# mcu.net
KiCad netlist of a schematic drawn in Altium Designer
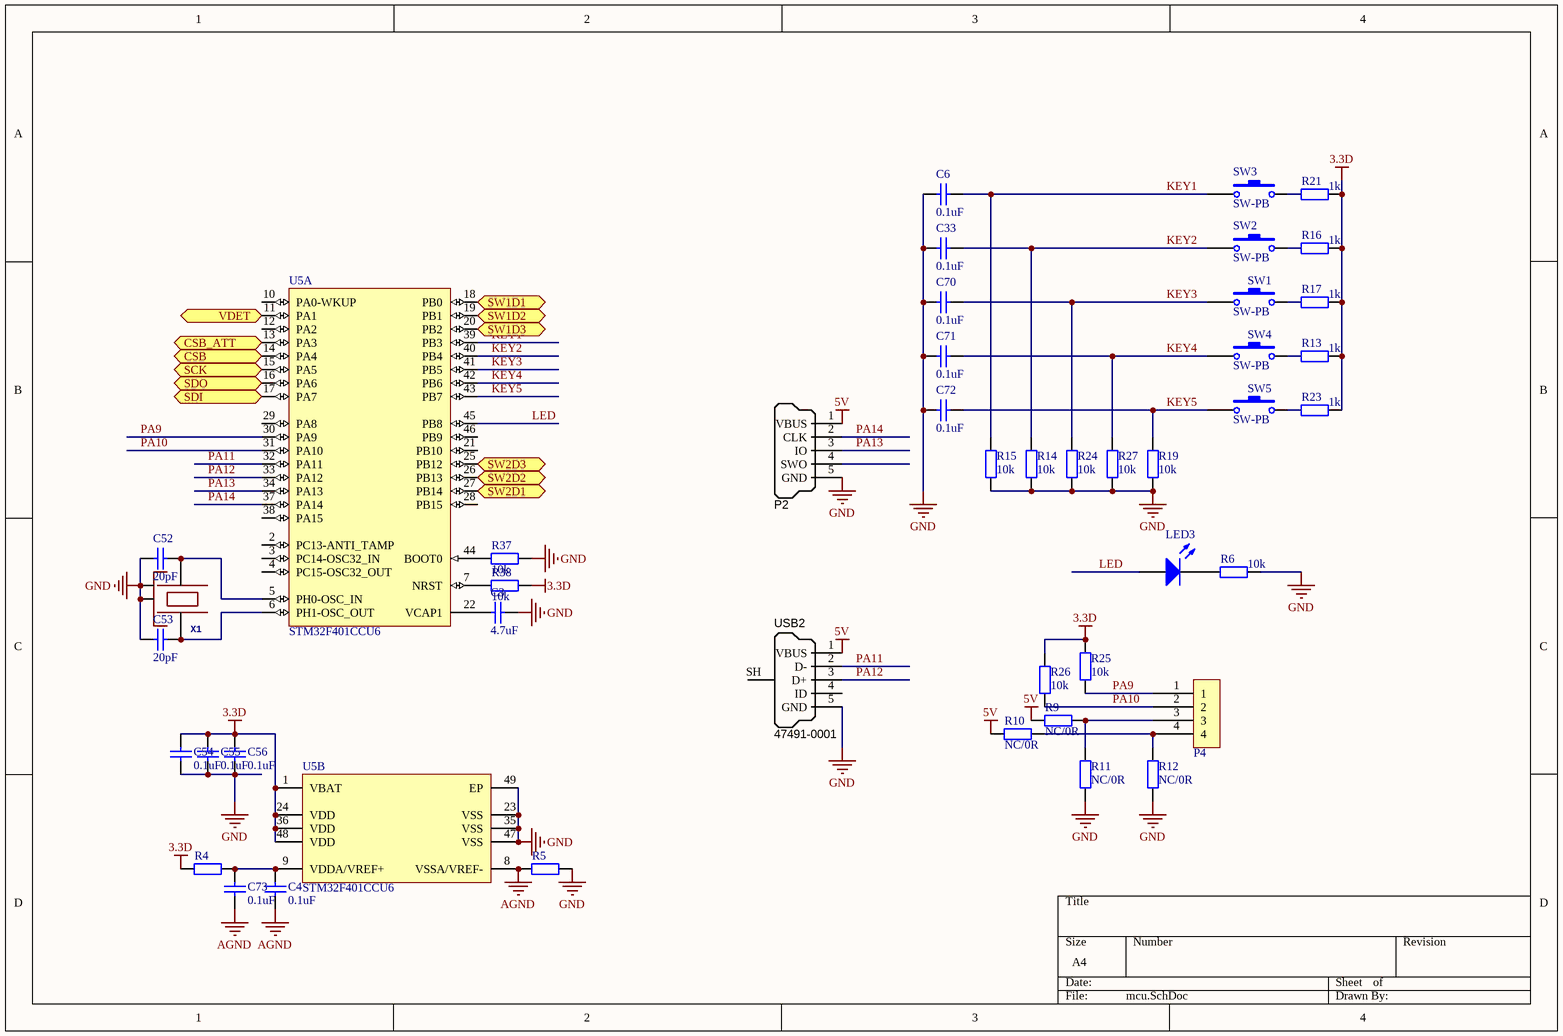
[diagram p0: mcu.SchDoc]

(export (version "E")
  (design (tool "Eeschema 10.0.6"))
  (components
    (comp (ref "C3")
      (value "4.7uF")
      (footprint "0603")
      (description "Capacitor")
      (fields (field (name "Comment") "Cap") (field (name "PUBLISHER") "Altium Limited"))
      (libsource (lib "RTC6705") (part "Cap"))
    )
    (comp (ref "C4")
      (value "0.1uF")
      (footprint "0402")
      (description "Capacitor")
      (fields (field (name "Comment") "Cap") (field (name "PUBLISHER") "Altium Limited"))
      (libsource (lib "RTC6705") (part "Cap"))
    )
    (comp (ref "C6")
      (value "0.1uF")
      (footprint "0402")
      (description "Capacitor")
      (fields (field (name "Comment") "Cap") (field (name "PUBLISHER") "Altium Limited"))
      (libsource (lib "RTC6705") (part "Cap"))
    )
    (comp (ref "C33")
      (value "0.1uF")
      (footprint "0402")
      (description "Capacitor")
      (fields (field (name "Comment") "Cap") (field (name "PUBLISHER") "Altium Limited"))
      (libsource (lib "RTC6705") (part "Cap"))
    )
    (comp (ref "C52")
      (value "20pF")
      (footprint "0402")
      (description "Capacitor")
      (fields (field (name "Comment") "Cap") (field (name "PUBLISHER") "Altium Limited"))
      (libsource (lib "RTC6705") (part "Cap"))
    )
    (comp (ref "C53")
      (value "20pF")
      (footprint "0402")
      (description "Capacitor")
      (fields (field (name "Comment") "Cap") (field (name "PUBLISHER") "Altium Limited"))
      (libsource (lib "RTC6705") (part "Cap"))
    )
    (comp (ref "C54")
      (value "0.1uF")
      (footprint "0402")
      (description "Capacitor")
      (fields (field (name "Comment") "Cap") (field (name "PUBLISHER") "Altium Limited"))
      (libsource (lib "RTC6705") (part "Cap"))
    )
    (comp (ref "C55")
      (value "0.1uF")
      (footprint "0402")
      (description "Capacitor")
      (fields (field (name "Comment") "Cap") (field (name "PUBLISHER") "Altium Limited"))
      (libsource (lib "RTC6705") (part "Cap"))
    )
    (comp (ref "C56")
      (value "0.1uF")
      (footprint "0402")
      (description "Capacitor")
      (fields (field (name "Comment") "Cap") (field (name "PUBLISHER") "Altium Limited"))
      (libsource (lib "RTC6705") (part "Cap"))
    )
    (comp (ref "C70")
      (value "0.1uF")
      (footprint "0402")
      (description "Capacitor")
      (fields (field (name "Comment") "Cap") (field (name "PUBLISHER") "Altium Limited"))
      (libsource (lib "RTC6705") (part "Cap"))
    )
    (comp (ref "C71")
      (value "0.1uF")
      (footprint "0402")
      (description "Capacitor")
      (fields (field (name "Comment") "Cap") (field (name "PUBLISHER") "Altium Limited"))
      (libsource (lib "RTC6705") (part "Cap"))
    )
    (comp (ref "C72")
      (value "0.1uF")
      (footprint "0402")
      (description "Capacitor")
      (fields (field (name "Comment") "Cap") (field (name "PUBLISHER") "Altium Limited"))
      (libsource (lib "RTC6705") (part "Cap"))
    )
    (comp (ref "C73")
      (value "0.1uF")
      (footprint "0402")
      (description "Capacitor")
      (fields (field (name "Comment") "Cap") (field (name "PUBLISHER") "Altium Limited"))
      (libsource (lib "RTC6705") (part "Cap"))
    )
    (comp (ref "LED3")
      (value "LED0")
      (footprint "0603")
      (description "Typical INFRARED GaAs LED")
      (fields (field (name "PUBLISHER") "Altium Limited"))
      (libsource (lib "Miscellaneous Devices") (part "LED0"))
    )
    (comp (ref "P2")
      (value "SWD_MicroUSB")
      (footprint "MICRO-YZX")
      (description "Connector SMD USB Micro Type B middle mount")
      (libsource (lib "sch") (part "SWD_MicroUSB"))
    )
    (comp (ref "P4") (value "UART/I2C") (footprint "4pSocket") (libsource (lib "sch") (part "4PSocket")))
    (comp (ref "R4")
      (value "0R/FB")
      (footprint "0402")
      (description "Resistor")
      (fields (field (name "PUBLISHER") "Altium Limited"))
      (libsource (lib "RTC6705") (part "Res2"))
    )
    (comp (ref "R5")
      (value "0R/FB")
      (footprint "0402")
      (description "Resistor")
      (fields (field (name "PUBLISHER") "Altium Limited"))
      (libsource (lib "RTC6705") (part "Res2"))
    )
    (comp (ref "R6")
      (value "10k")
      (footprint "0402")
      (description "Resistor")
      (fields (field (name "PUBLISHER") "Altium Limited"))
      (libsource (lib "Miscellaneous Devices") (part "Res2"))
    )
    (comp (ref "R9")
      (value "NC/0R")
      (footprint "0402")
      (description "Resistor")
      (fields (field (name "PUBLISHER") "Altium Limited"))
      (libsource (lib "") (part "Res2_2"))
    )
    (comp (ref "R10")
      (value "NC/0R")
      (footprint "0402")
      (description "Resistor")
      (fields (field (name "PUBLISHER") "Altium Limited"))
      (libsource (lib "") (part "Res2_2"))
    )
    (comp (ref "R11")
      (value "NC/0R")
      (footprint "0402")
      (description "Resistor")
      (fields (field (name "PUBLISHER") "Altium Limited"))
      (libsource (lib "") (part "Res2_1"))
    )
    (comp (ref "R12")
      (value "NC/0R")
      (footprint "0402")
      (description "Resistor")
      (fields (field (name "PUBLISHER") "Altium Limited"))
      (libsource (lib "") (part "Res2_1"))
    )
    (comp (ref "R13")
      (value "1k")
      (footprint "0402")
      (description "Resistor")
      (fields (field (name "PUBLISHER") "Altium Limited"))
      (libsource (lib "Miscellaneous Devices") (part "Res2"))
    )
    (comp (ref "R14")
      (value "10k")
      (footprint "0402")
      (description "Resistor")
      (fields (field (name "PUBLISHER") "Altium Limited"))
      (libsource (lib "") (part "Res2_1"))
    )
    (comp (ref "R15")
      (value "10k")
      (footprint "0402")
      (description "Resistor")
      (fields (field (name "PUBLISHER") "Altium Limited"))
      (libsource (lib "") (part "Res2_1"))
    )
    (comp (ref "R16")
      (value "1k")
      (footprint "0402")
      (description "Resistor")
      (fields (field (name "PUBLISHER") "Altium Limited"))
      (libsource (lib "Miscellaneous Devices") (part "Res2"))
    )
    (comp (ref "R17")
      (value "1k")
      (footprint "0402")
      (description "Resistor")
      (fields (field (name "PUBLISHER") "Altium Limited"))
      (libsource (lib "Miscellaneous Devices") (part "Res2"))
    )
    (comp (ref "R19")
      (value "10k")
      (footprint "0402")
      (description "Resistor")
      (fields (field (name "PUBLISHER") "Altium Limited"))
      (libsource (lib "") (part "Res2_1"))
    )
    (comp (ref "R21")
      (value "1k")
      (footprint "0402")
      (description "Resistor")
      (fields (field (name "PUBLISHER") "Altium Limited"))
      (libsource (lib "Miscellaneous Devices") (part "Res2"))
    )
    (comp (ref "R23")
      (value "1k")
      (footprint "0402")
      (description "Resistor")
      (fields (field (name "PUBLISHER") "Altium Limited"))
      (libsource (lib "Miscellaneous Devices") (part "Res2"))
    )
    (comp (ref "R24")
      (value "10k")
      (footprint "0402")
      (description "Resistor")
      (fields (field (name "PUBLISHER") "Altium Limited"))
      (libsource (lib "") (part "Res2_1"))
    )
    (comp (ref "R25")
      (value "10k")
      (footprint "0402")
      (description "Resistor")
      (fields (field (name "PUBLISHER") "Altium Limited"))
      (libsource (lib "") (part "Res2_1"))
    )
    (comp (ref "R26")
      (value "10k")
      (footprint "0402")
      (description "Resistor")
      (fields (field (name "PUBLISHER") "Altium Limited"))
      (libsource (lib "") (part "Res2_1"))
    )
    (comp (ref "R27")
      (value "10k")
      (footprint "0402")
      (description "Resistor")
      (fields (field (name "PUBLISHER") "Altium Limited"))
      (libsource (lib "") (part "Res2_1"))
    )
    (comp (ref "R37")
      (value "10k")
      (footprint "0402")
      (description "Resistor")
      (fields (field (name "Comment") "Res2") (field (name "PUBLISHER") "Altium Limited"))
      (libsource (lib "") (part "Res2_1"))
    )
    (comp (ref "R38")
      (value "10k")
      (footprint "0402")
      (description "Resistor")
      (fields (field (name "Comment") "Res2") (field (name "PUBLISHER") "Altium Limited"))
      (libsource (lib "RTC6705") (part "Res2"))
    )
    (comp (ref "SW1")
      (value "SW-PB")
      (footprint "SW3x4")
      (description "Switch")
      (fields (field (name "PUBLISHER") "Altium Limited"))
      (libsource (lib "Miscellaneous Devices") (part "SW-PB"))
    )
    (comp (ref "SW2")
      (value "SW-PB")
      (footprint "SW3x4")
      (description "Switch")
      (fields (field (name "PUBLISHER") "Altium Limited"))
      (libsource (lib "Miscellaneous Devices") (part "SW-PB"))
    )
    (comp (ref "SW3")
      (value "SW-PB")
      (footprint "SW3x4")
      (description "Switch")
      (fields (field (name "PUBLISHER") "Altium Limited"))
      (libsource (lib "Miscellaneous Devices") (part "SW-PB"))
    )
    (comp (ref "SW4")
      (value "SW-PB")
      (footprint "SW3x4")
      (description "Switch")
      (fields (field (name "PUBLISHER") "Altium Limited"))
      (libsource (lib "Miscellaneous Devices") (part "SW-PB"))
    )
    (comp (ref "SW5")
      (value "SW-PB")
      (footprint "SW3x4")
      (description "Switch")
      (fields (field (name "PUBLISHER") "Altium Limited"))
      (libsource (lib "Miscellaneous Devices") (part "SW-PB"))
    )
    (comp (ref "U5")
      (value "STM32F401CCU6")
      (footprint "STM-UFQFPN48_N")
      (fields (field (name "MANUFACTURER") "STMicroelectronics"))
      (libsource (lib "STMicroelectronics STM32 F4") (part "STM32F401CCU6"))
    )
    (comp (ref "USB2")
      (value "USB Micro Type B")
      (footprint "MICRO-YZX")
      (description "Connector SMD USB Micro Type B middle mount")
      (fields (field (name "MANUFACTURER PART NUMBER 1") "47491-0001"))
      (libsource (lib "PBL - Connectors") (part "USB_Micro_TypeB"))
    )
    (comp (ref "X1")
      (value "24.000 KHz 3.2x2.5mm 8-10pf")
      (footprint "OSCILLATOR-3.2X2.5")
      (description "Crystal Oscillator in 3.2x2.5 SMD")
      (libsource (lib "pixhawk2") (part "OSCILLATOR-3.2X2.5"))
    )
  )
  (nets
    (net (code "1") (name "/CSB") (class "Default")
      (node (ref "U5") (pin "14") (pinfunction "PA4_14") (pintype "bidirectional"))
    )
    (net (code "2") (name "/CSB_ATT") (class "Default")
      (node (ref "U5") (pin "13") (pinfunction "PA3_13") (pintype "bidirectional"))
    )
    (net (code "3") (name "/KEY1") (class "Default")
      (node (ref "C6") (pin "2") (pinfunction "2_2") (pintype "passive"))
      (node (ref "R15") (pin "2") (pinfunction "2_2") (pintype "passive"))
      (node (ref "SW3") (pin "1") (pinfunction "1_1") (pintype "passive"))
      (node (ref "U5") (pin "39") (pinfunction "PB3_39") (pintype "bidirectional"))
    )
    (net (code "4") (name "/KEY2") (class "Default")
      (node (ref "C33") (pin "1") (pinfunction "1_1") (pintype "passive"))
      (node (ref "R14") (pin "2") (pinfunction "2_2") (pintype "passive"))
      (node (ref "SW2") (pin "1") (pinfunction "1_1") (pintype "passive"))
      (node (ref "U5") (pin "40") (pinfunction "PB4_40") (pintype "bidirectional"))
    )
    (net (code "5") (name "/KEY3") (class "Default")
      (node (ref "C70") (pin "1") (pinfunction "1_1") (pintype "passive"))
      (node (ref "R24") (pin "2") (pinfunction "2_2") (pintype "passive"))
      (node (ref "SW1") (pin "1") (pinfunction "1_1") (pintype "passive"))
      (node (ref "U5") (pin "41") (pinfunction "PB5_41") (pintype "bidirectional"))
    )
    (net (code "6") (name "/KEY4") (class "Default")
      (node (ref "C71") (pin "1") (pinfunction "1_1") (pintype "passive"))
      (node (ref "R27") (pin "2") (pinfunction "2_2") (pintype "passive"))
      (node (ref "SW4") (pin "1") (pinfunction "1_1") (pintype "passive"))
      (node (ref "U5") (pin "42") (pinfunction "PB6_42") (pintype "bidirectional"))
    )
    (net (code "7") (name "/KEY5") (class "Default")
      (node (ref "C72") (pin "1") (pinfunction "1_1") (pintype "passive"))
      (node (ref "R19") (pin "2") (pinfunction "2_2") (pintype "passive"))
      (node (ref "SW5") (pin "1") (pinfunction "1_1") (pintype "passive"))
      (node (ref "U5") (pin "43") (pinfunction "PB7_43") (pintype "bidirectional"))
    )
    (net (code "8") (name "/LED") (class "Default")
      (node (ref "LED3") (pin "1") (pinfunction "A_1") (pintype "passive"))
      (node (ref "U5") (pin "45") (pinfunction "PB8_45") (pintype "bidirectional"))
    )
    (net (code "9") (name "/PA9") (class "Default")
      (node (ref "P4") (pin "1") (pinfunction "1_1") (pintype "passive"))
      (node (ref "R25") (pin "1") (pinfunction "1_1") (pintype "passive"))
      (node (ref "U5") (pin "30") (pinfunction "PA9_30") (pintype "bidirectional"))
    )
    (net (code "10") (name "/PA10") (class "Default")
      (node (ref "P4") (pin "2") (pinfunction "2_2") (pintype "passive"))
      (node (ref "R26") (pin "1") (pinfunction "1_1") (pintype "passive"))
      (node (ref "U5") (pin "31") (pinfunction "PA10_31") (pintype "bidirectional"))
    )
    (net (code "11") (name "/PA11") (class "Default")
      (node (ref "U5") (pin "32") (pinfunction "PA11_32") (pintype "bidirectional"))
      (node (ref "USB2") (pin "2") (pinfunction "D-_2") (pintype "passive"))
    )
    (net (code "12") (name "/PA12") (class "Default")
      (node (ref "U5") (pin "33") (pinfunction "PA12_33") (pintype "bidirectional"))
      (node (ref "USB2") (pin "3") (pinfunction "D+_3") (pintype "passive"))
    )
    (net (code "13") (name "/PA13") (class "Default")
      (node (ref "P2") (pin "3") (pinfunction "IO_3") (pintype "passive"))
      (node (ref "U5") (pin "34") (pinfunction "PA13_34") (pintype "bidirectional"))
    )
    (net (code "14") (name "/PA14") (class "Default")
      (node (ref "P2") (pin "2") (pinfunction "CLK_2") (pintype "passive"))
      (node (ref "U5") (pin "37") (pinfunction "PA14_37") (pintype "bidirectional"))
    )
    (net (code "15") (name "/SCK") (class "Default")
      (node (ref "U5") (pin "15") (pinfunction "PA5_15") (pintype "bidirectional"))
    )
    (net (code "16") (name "/SDI") (class "Default")
      (node (ref "U5") (pin "17") (pinfunction "PA7_17") (pintype "bidirectional"))
    )
    (net (code "17") (name "/SDO") (class "Default")
      (node (ref "U5") (pin "16") (pinfunction "PA6_16") (pintype "bidirectional"))
    )
    (net (code "18") (name "/SW1D1") (class "Default")
      (node (ref "U5") (pin "18") (pinfunction "PB0_18") (pintype "bidirectional"))
    )
    (net (code "19") (name "/SW1D2") (class "Default")
      (node (ref "U5") (pin "19") (pinfunction "PB1_19") (pintype "bidirectional"))
    )
    (net (code "20") (name "/SW1D3") (class "Default")
      (node (ref "U5") (pin "20") (pinfunction "PB2_20") (pintype "bidirectional"))
    )
    (net (code "21") (name "/SW2D1") (class "Default")
      (node (ref "U5") (pin "27") (pinfunction "PB14_27") (pintype "bidirectional"))
    )
    (net (code "22") (name "/SW2D2") (class "Default")
      (node (ref "U5") (pin "26") (pinfunction "PB13_26") (pintype "bidirectional"))
    )
    (net (code "23") (name "/SW2D3") (class "Default")
      (node (ref "U5") (pin "25") (pinfunction "PB12_25") (pintype "bidirectional"))
    )
    (net (code "24") (name "/VDET") (class "Default")
      (node (ref "U5") (pin "11") (pinfunction "PA1_11") (pintype "bidirectional"))
    )
    (net (code "25") (name "3.3D") (class "Default")
      (node (ref "C54") (pin "2") (pinfunction "2_2") (pintype "passive"))
      (node (ref "C55") (pin "2") (pinfunction "2_2") (pintype "passive"))
      (node (ref "C56") (pin "2") (pinfunction "2_2") (pintype "passive"))
      (node (ref "R13") (pin "2") (pinfunction "2_2") (pintype "passive"))
      (node (ref "R16") (pin "2") (pinfunction "2_2") (pintype "passive"))
      (node (ref "R17") (pin "2") (pinfunction "2_2") (pintype "passive"))
      (node (ref "R21") (pin "2") (pinfunction "2_2") (pintype "passive"))
      (node (ref "R23") (pin "2") (pinfunction "2_2") (pintype "passive"))
      (node (ref "R25") (pin "2") (pinfunction "2_2") (pintype "passive"))
      (node (ref "R26") (pin "2") (pinfunction "2_2") (pintype "passive"))
      (node (ref "R38") (pin "1") (pinfunction "1_1") (pintype "passive"))
      (node (ref "R4") (pin "2") (pinfunction "2_2") (pintype "passive"))
      (node (ref "U5") (pin "1") (pinfunction "VBAT_1") (pintype "power_in"))
      (node (ref "U5") (pin "24") (pinfunction "VDD_24") (pintype "power_in"))
      (node (ref "U5") (pin "36") (pinfunction "VDD_36") (pintype "power_in"))
      (node (ref "U5") (pin "48") (pinfunction "VDD_48") (pintype "power_in"))
    )
    (net (code "26") (name "5V") (class "Default")
      (node (ref "P2") (pin "1") (pinfunction "VBUS_1") (pintype "passive"))
      (node (ref "R10") (pin "2") (pinfunction "2_2") (pintype "passive"))
      (node (ref "R9") (pin "2") (pinfunction "2_2") (pintype "passive"))
      (node (ref "USB2") (pin "1") (pinfunction "VBUS_1") (pintype "passive"))
    )
    (net (code "27") (name "AGND") (class "Default")
      (node (ref "C4") (pin "1") (pinfunction "1_1") (pintype "passive"))
      (node (ref "C73") (pin "1") (pinfunction "1_1") (pintype "passive"))
      (node (ref "R5") (pin "2") (pinfunction "2_2") (pintype "passive"))
      (node (ref "U5") (pin "8") (pinfunction "VSSA/VREF-_8") (pintype "power_in"))
    )
    (net (code "28") (name "GND") (class "Default")
      (node (ref "C3") (pin "1") (pinfunction "1_1") (pintype "passive"))
      (node (ref "C33") (pin "2") (pinfunction "2_2") (pintype "passive"))
      (node (ref "C52") (pin "1") (pinfunction "1_1") (pintype "passive"))
      (node (ref "C53") (pin "1") (pinfunction "1_1") (pintype "passive"))
      (node (ref "C54") (pin "1") (pinfunction "1_1") (pintype "passive"))
      (node (ref "C55") (pin "1") (pinfunction "1_1") (pintype "passive"))
      (node (ref "C56") (pin "1") (pinfunction "1_1") (pintype "passive"))
      (node (ref "C6") (pin "1") (pinfunction "1_1") (pintype "passive"))
      (node (ref "C70") (pin "2") (pinfunction "2_2") (pintype "passive"))
      (node (ref "C71") (pin "2") (pinfunction "2_2") (pintype "passive"))
      (node (ref "C72") (pin "2") (pinfunction "2_2") (pintype "passive"))
      (node (ref "P2") (pin "5") (pinfunction "GND_5") (pintype "passive"))
      (node (ref "R11") (pin "1") (pinfunction "1_1") (pintype "passive"))
      (node (ref "R12") (pin "1") (pinfunction "1_1") (pintype "passive"))
      (node (ref "R14") (pin "1") (pinfunction "1_1") (pintype "passive"))
      (node (ref "R15") (pin "1") (pinfunction "1_1") (pintype "passive"))
      (node (ref "R19") (pin "1") (pinfunction "1_1") (pintype "passive"))
      (node (ref "R24") (pin "1") (pinfunction "1_1") (pintype "passive"))
      (node (ref "R27") (pin "1") (pinfunction "1_1") (pintype "passive"))
      (node (ref "R37") (pin "2") (pinfunction "2_2") (pintype "passive"))
      (node (ref "R5") (pin "1") (pinfunction "1_1") (pintype "passive"))
      (node (ref "R6") (pin "2") (pinfunction "2_2") (pintype "passive"))
      (node (ref "U5") (pin "23") (pinfunction "VSS_23") (pintype "power_in"))
      (node (ref "U5") (pin "35") (pinfunction "VSS_35") (pintype "power_in"))
      (node (ref "U5") (pin "47") (pinfunction "VSS_47") (pintype "power_in"))
      (node (ref "U5") (pin "49") (pinfunction "EP_49") (pintype "power_in"))
      (node (ref "USB2") (pin "5") (pinfunction "GND_5") (pintype "passive"))
      (node (ref "X1") (pin "2") (pinfunction "NC_2_2") (pintype "open_emitter"))
      (node (ref "X1") (pin "4") (pinfunction "NC_4_4") (pintype "open_emitter"))
    )
    (net (code "29") (name "Net-(LED3-K)") (class "Default")
      (node (ref "LED3") (pin "2") (pinfunction "K_2") (pintype "passive"))
      (node (ref "R6") (pin "1") (pinfunction "1_1") (pintype "passive"))
    )
    (net (code "30") (name "Net-(P4-Pad3)") (class "Default")
      (node (ref "P4") (pin "3") (pinfunction "3_3") (pintype "passive"))
      (node (ref "R11") (pin "2") (pinfunction "2_2") (pintype "passive"))
      (node (ref "R9") (pin "1") (pinfunction "1_1") (pintype "passive"))
    )
    (net (code "31") (name "Net-(P4-Pad4)") (class "Default")
      (node (ref "P4") (pin "4") (pinfunction "4_4") (pintype "passive"))
      (node (ref "R10") (pin "1") (pinfunction "1_1") (pintype "passive"))
      (node (ref "R12") (pin "2") (pinfunction "2_2") (pintype "passive"))
    )
    (net (code "32") (name "Net-(R13-Pad1)") (class "Default")
      (node (ref "R13") (pin "1") (pinfunction "1_1") (pintype "passive"))
      (node (ref "SW4") (pin "2") (pinfunction "2_2") (pintype "passive"))
    )
    (net (code "33") (name "Net-(R16-Pad1)") (class "Default")
      (node (ref "R16") (pin "1") (pinfunction "1_1") (pintype "passive"))
      (node (ref "SW2") (pin "2") (pinfunction "2_2") (pintype "passive"))
    )
    (net (code "34") (name "Net-(R17-Pad1)") (class "Default")
      (node (ref "R17") (pin "1") (pinfunction "1_1") (pintype "passive"))
      (node (ref "SW1") (pin "2") (pinfunction "2_2") (pintype "passive"))
    )
    (net (code "35") (name "Net-(R21-Pad1)") (class "Default")
      (node (ref "R21") (pin "1") (pinfunction "1_1") (pintype "passive"))
      (node (ref "SW3") (pin "2") (pinfunction "2_2") (pintype "passive"))
    )
    (net (code "36") (name "Net-(R23-Pad1)") (class "Default")
      (node (ref "R23") (pin "1") (pinfunction "1_1") (pintype "passive"))
      (node (ref "SW5") (pin "2") (pinfunction "2_2") (pintype "passive"))
    )
    (net (code "37") (name "Net-(U5A-BOOT0)") (class "Default")
      (node (ref "R37") (pin "1") (pinfunction "1_1") (pintype "passive"))
      (node (ref "U5") (pin "44") (pinfunction "BOOT0_44") (pintype "input"))
    )
    (net (code "38") (name "Net-(U5A-NRST)") (class "Default")
      (node (ref "R38") (pin "2") (pinfunction "2_2") (pintype "passive"))
      (node (ref "U5") (pin "7") (pinfunction "NRST_7") (pintype "bidirectional"))
    )
    (net (code "39") (name "Net-(U5A-PH0-OSC_IN)") (class "Default")
      (node (ref "C52") (pin "2") (pinfunction "2_2") (pintype "passive"))
      (node (ref "U5") (pin "5") (pinfunction "PH0-OSC_IN_5") (pintype "bidirectional"))
      (node (ref "X1") (pin "1") (pinfunction "1_1") (pintype "passive"))
    )
    (net (code "40") (name "Net-(U5A-PH1-OSC_OUT)") (class "Default")
      (node (ref "C53") (pin "2") (pinfunction "2_2") (pintype "passive"))
      (node (ref "U5") (pin "6") (pinfunction "PH1-OSC_OUT_6") (pintype "bidirectional"))
      (node (ref "X1") (pin "3") (pinfunction "3_3") (pintype "passive"))
    )
    (net (code "41") (name "Net-(U5A-VCAP1)") (class "Default")
      (node (ref "C3") (pin "2") (pinfunction "2_2") (pintype "passive"))
      (node (ref "U5") (pin "22") (pinfunction "VCAP1_22") (pintype "power_in"))
    )
    (net (code "42") (name "Net-(U5B-VDDA{slash}VREF+)") (class "Default")
      (node (ref "C4") (pin "2") (pinfunction "2_2") (pintype "passive"))
      (node (ref "C73") (pin "2") (pinfunction "2_2") (pintype "passive"))
      (node (ref "R4") (pin "1") (pinfunction "1_1") (pintype "passive"))
      (node (ref "U5") (pin "9") (pinfunction "VDDA/VREF+_9") (pintype "power_in"))
    )
    (net (code "43") (name "unconnected-(P2-SWO-Pad4)") (class "Default")
      (node (ref "P2") (pin "4") (pinfunction "SWO_4") (pintype "passive"))
    )
    (net (code "44") (name "unconnected-(U5A-PA0-WKUP-Pad10)") (class "Default")
      (node (ref "U5") (pin "10") (pinfunction "PA0-WKUP_10") (pintype "bidirectional"))
    )
    (net (code "45") (name "unconnected-(U5A-PA2-Pad12)") (class "Default")
      (node (ref "U5") (pin "12") (pinfunction "PA2_12") (pintype "bidirectional"))
    )
    (net (code "46") (name "unconnected-(U5A-PA8-Pad29)") (class "Default")
      (node (ref "U5") (pin "29") (pinfunction "PA8_29") (pintype "bidirectional"))
    )
    (net (code "47") (name "unconnected-(U5A-PA15-Pad38)") (class "Default")
      (node (ref "U5") (pin "38") (pinfunction "PA15_38") (pintype "bidirectional"))
    )
    (net (code "48") (name "unconnected-(U5A-PB9-Pad46)") (class "Default")
      (node (ref "U5") (pin "46") (pinfunction "PB9_46") (pintype "bidirectional"))
    )
    (net (code "49") (name "unconnected-(U5A-PB10-Pad21)") (class "Default")
      (node (ref "U5") (pin "21") (pinfunction "PB10_21") (pintype "bidirectional"))
    )
    (net (code "50") (name "unconnected-(U5A-PB15-Pad28)") (class "Default")
      (node (ref "U5") (pin "28") (pinfunction "PB15_28") (pintype "bidirectional"))
    )
    (net (code "51") (name "unconnected-(U5A-PC13-ANTI_TAMP-Pad2)") (class "Default")
      (node (ref "U5") (pin "2") (pinfunction "PC13-ANTI_TAMP_2") (pintype "bidirectional"))
    )
    (net (code "52") (name "unconnected-(U5A-PC14-OSC32_IN-Pad3)") (class "Default")
      (node (ref "U5") (pin "3") (pinfunction "PC14-OSC32_IN_3") (pintype "bidirectional"))
    )
    (net (code "53") (name "unconnected-(U5A-PC15-OSC32_OUT-Pad4)") (class "Default")
      (node (ref "U5") (pin "4") (pinfunction "PC15-OSC32_OUT_4") (pintype "bidirectional"))
    )
    (net (code "54") (name "unconnected-(USB2-ID-Pad4)") (class "Default")
      (node (ref "USB2") (pin "4") (pinfunction "ID_4") (pintype "passive"))
    )
    (net (code "55") (name "unconnected-(USB2-Shell-PadSH)") (class "Default")
      (node (ref "USB2") (pin "SH") (pinfunction "Shell_SH") (pintype "passive"))
    )
  )
)
